# Versterker.net
KiCad netlist of a schematic drawn in Altium Designer
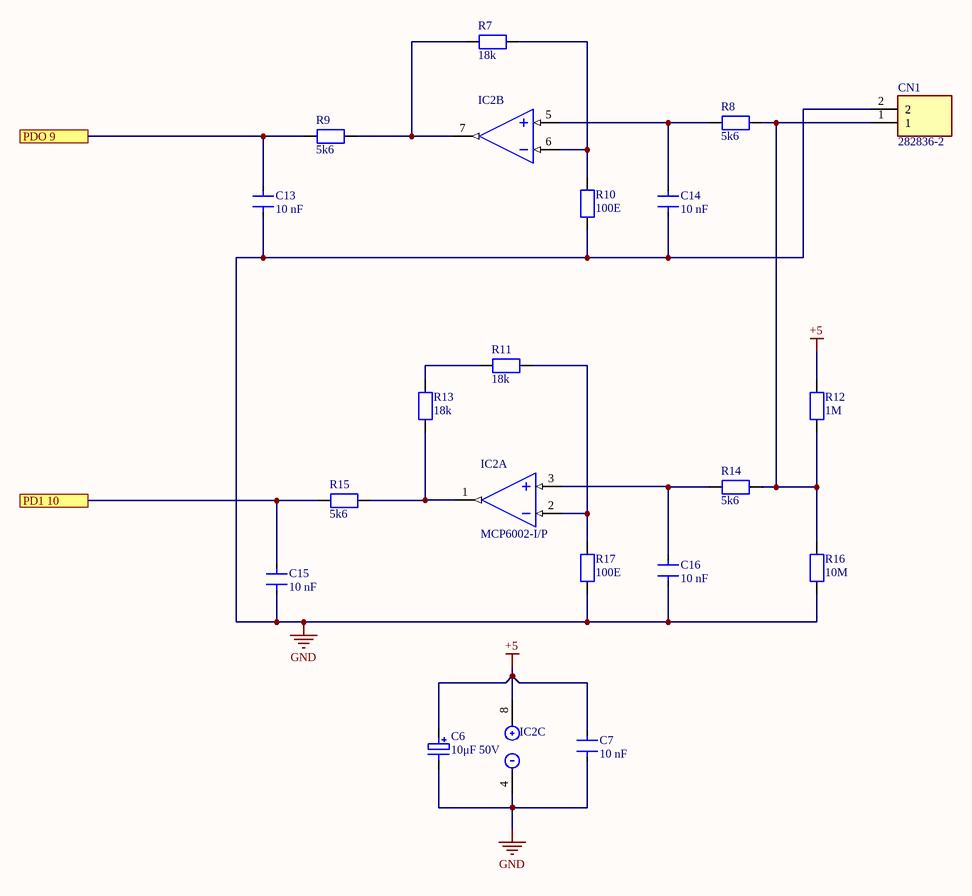
[diagram p0: Versterker.SchDoc]

(export (version "E")
  (design (tool "Eeschema 10.0.6"))
  (components
    (comp (ref "C6")
      (value "10μF 50V")
      (footprint "Elco 10uF 50V")
      (fields
        (field (name "PART NUMBER") "02015A270JAT2A")
        (field (name "MANUFACTURER") "AVX Interconnect / Elco")
      )
      (libsource (lib "Soldeerstation") (part "Condensator Elco"))
    )
    (comp (ref "C7")
      (value "10 nF")
      (footprint "0805")
      (description "Chip Multilayer Ceramic Capacitors for General Purpose, 0805, 10uF, X5R, 15%, 10%, 25V")
      (fields (field (name "VOLTAGE") "25V") (field (name "TOLERANCE") "10%"))
      (libsource (lib "Soldeerstation") (part "Condensator 0805"))
    )
    (comp (ref "C13")
      (value "10 nF")
      (footprint "0805")
      (description "Chip Multilayer Ceramic Capacitors for General Purpose, 0805, 10uF, X5R, 15%, 10%, 25V")
      (fields (field (name "VOLTAGE") "25V") (field (name "TOLERANCE") "10%"))
      (libsource (lib "Soldeerstation") (part "Condensator 0805"))
    )
    (comp (ref "C14")
      (value "10 nF")
      (footprint "0805")
      (description "Chip Multilayer Ceramic Capacitors for General Purpose, 0805, 10uF, X5R, 15%, 10%, 25V")
      (fields (field (name "VOLTAGE") "25V") (field (name "TOLERANCE") "10%"))
      (libsource (lib "Soldeerstation") (part "Condensator 0805"))
    )
    (comp (ref "C15")
      (value "10 nF")
      (footprint "0805")
      (description "Chip Multilayer Ceramic Capacitors for General Purpose, 0805, 10uF, X5R, 15%, 10%, 25V")
      (fields (field (name "VOLTAGE") "25V") (field (name "TOLERANCE") "10%"))
      (libsource (lib "Soldeerstation") (part "Condensator 0805"))
    )
    (comp (ref "C16")
      (value "10 nF")
      (footprint "0805")
      (description "Chip Multilayer Ceramic Capacitors for General Purpose, 0805, 10uF, X5R, 15%, 10%, 25V")
      (fields (field (name "VOLTAGE") "25V") (field (name "TOLERANCE") "10%"))
      (libsource (lib "Soldeerstation") (part "Condensator 0805"))
    )
    (comp (ref "CN1")
      (value "282836-2")
      (footprint "Schroefconnector 2 Pin")
      (description "Connector")
      (libsource (lib "Soldeerstation") (part "Schroefconnector 2 Pin L"))
    )
    (comp (ref "IC2")
      (value "MCP6002-I/P")
      (footprint "Opamp")
      (description "AMP-OPA-MCP6002-IL8")
      (libsource (lib "Soldeerstation") (part "Opamp"))
    )
    (comp (ref "R7")
      (value "18k")
      (footprint "Resistor")
      (description "Resistor")
      (fields (field (name "MANUFACTURER") "Vishay Dale") (field (name "PART NUMBER") "CRCW08050000Z0EA"))
      (libsource (lib "Soldeerstation") (part "Resistor"))
    )
    (comp (ref "R8")
      (value "5k6")
      (footprint "Resistor")
      (description "Resistor")
      (fields (field (name "MANUFACTURER") "Vishay Dale") (field (name "PART NUMBER") "CRCW08050000Z0EA"))
      (libsource (lib "Soldeerstation") (part "Resistor"))
    )
    (comp (ref "R9")
      (value "5k6")
      (footprint "Resistor")
      (description "Resistor")
      (fields (field (name "MANUFACTURER") "Vishay Dale") (field (name "PART NUMBER") "CRCW08050000Z0EA"))
      (libsource (lib "Soldeerstation") (part "Resistor"))
    )
    (comp (ref "R10")
      (value "100E")
      (footprint "Resistor")
      (description "Resistor")
      (fields (field (name "MANUFACTURER") "Vishay Dale") (field (name "PART NUMBER") "CRCW08050000Z0EA"))
      (libsource (lib "Soldeerstation") (part "Resistor"))
    )
    (comp (ref "R11")
      (value "18k")
      (footprint "Resistor")
      (description "Resistor")
      (fields (field (name "MANUFACTURER") "Vishay Dale") (field (name "PART NUMBER") "CRCW08050000Z0EA"))
      (libsource (lib "Soldeerstation") (part "Resistor"))
    )
    (comp (ref "R12")
      (value "1M")
      (footprint "Resistor")
      (description "Resistor")
      (fields (field (name "MANUFACTURER") "Vishay Dale") (field (name "PART NUMBER") "CRCW08050000Z0EA"))
      (libsource (lib "Soldeerstation") (part "Resistor"))
    )
    (comp (ref "R13")
      (value "18k")
      (footprint "Resistor")
      (description "Resistor")
      (fields (field (name "MANUFACTURER") "Vishay Dale") (field (name "PART NUMBER") "CRCW08050000Z0EA"))
      (libsource (lib "Soldeerstation") (part "Resistor"))
    )
    (comp (ref "R14")
      (value "5k6")
      (footprint "Resistor")
      (description "Resistor")
      (fields (field (name "MANUFACTURER") "Vishay Dale") (field (name "PART NUMBER") "CRCW08050000Z0EA"))
      (libsource (lib "Soldeerstation") (part "Resistor"))
    )
    (comp (ref "R15")
      (value "5k6")
      (footprint "Resistor")
      (description "Resistor")
      (fields (field (name "MANUFACTURER") "Vishay Dale") (field (name "PART NUMBER") "CRCW08050000Z0EA"))
      (libsource (lib "Soldeerstation") (part "Resistor"))
    )
    (comp (ref "R16")
      (value "10M")
      (footprint "Resistor")
      (description "Resistor")
      (fields (field (name "MANUFACTURER") "Vishay Dale") (field (name "PART NUMBER") "CRCW08050000Z0EA"))
      (libsource (lib "Soldeerstation") (part "Resistor"))
    )
    (comp (ref "R17")
      (value "100E")
      (footprint "Resistor")
      (description "Resistor")
      (fields (field (name "MANUFACTURER") "Vishay Dale") (field (name "PART NUMBER") "CRCW08050000Z0EA"))
      (libsource (lib "Soldeerstation") (part "Resistor"))
    )
  )
  (nets
    (net (code "1") (name "+5") (class "Default")
      (node (ref "C6") (pin "1") (pinfunction "1_1") (pintype "passive"))
      (node (ref "C7") (pin "2") (pinfunction "2_2") (pintype "passive"))
      (node (ref "IC2") (pin "8") (pintype "power_in"))
      (node (ref "R12") (pin "2") (pinfunction "2_2") (pintype "passive"))
    )
    (net (code "2") (name "/PD1 10") (class "Default")
      (node (ref "C15") (pin "2") (pinfunction "2_2") (pintype "passive"))
      (node (ref "R15") (pin "2") (pinfunction "2_2") (pintype "passive"))
    )
    (net (code "3") (name "/PDO 9") (class "Default")
      (node (ref "C13") (pin "2") (pinfunction "2_2") (pintype "passive"))
      (node (ref "R9") (pin "1") (pintype "passive"))
    )
    (net (code "4") (name "GND") (class "Default")
      (node (ref "C13") (pin "1") (pinfunction "1_1") (pintype "passive"))
      (node (ref "C14") (pin "1") (pinfunction "1_1") (pintype "passive"))
      (node (ref "C15") (pin "1") (pinfunction "1_1") (pintype "passive"))
      (node (ref "C16") (pin "1") (pinfunction "1_1") (pintype "passive"))
      (node (ref "C6") (pin "2") (pinfunction "2_2") (pintype "passive"))
      (node (ref "C7") (pin "1") (pinfunction "1_1") (pintype "passive"))
      (node (ref "CN1") (pin "2") (pinfunction "2_2") (pintype "passive"))
      (node (ref "IC2") (pin "4") (pintype "power_in"))
      (node (ref "R10") (pin "1") (pintype "passive"))
      (node (ref "R16") (pin "1") (pintype "passive"))
      (node (ref "R17") (pin "1") (pintype "passive"))
    )
    (net (code "5") (name "Net-(C14-Pad2)") (class "Default")
      (node (ref "C14") (pin "2") (pinfunction "2_2") (pintype "passive"))
      (node (ref "IC2") (pin "5") (pintype "input"))
      (node (ref "R8") (pin "1") (pintype "passive"))
    )
    (net (code "6") (name "Net-(C16-Pad2)") (class "Default")
      (node (ref "C16") (pin "2") (pinfunction "2_2") (pintype "passive"))
      (node (ref "IC2") (pin "3") (pintype "input"))
      (node (ref "R14") (pin "1") (pintype "passive"))
    )
    (net (code "7") (name "Net-(CN1-Pad1)") (class "Default")
      (node (ref "CN1") (pin "1") (pinfunction "1_1") (pintype "passive"))
      (node (ref "R12") (pin "1") (pintype "passive"))
      (node (ref "R14") (pin "2") (pinfunction "2_2") (pintype "passive"))
      (node (ref "R16") (pin "2") (pinfunction "2_2") (pintype "passive"))
      (node (ref "R8") (pin "2") (pinfunction "2_2") (pintype "passive"))
    )
    (net (code "8") (name "Net-(IC2-Pad1)") (class "Default")
      (node (ref "IC2") (pin "1") (pintype "output"))
      (node (ref "R13") (pin "1") (pintype "passive"))
      (node (ref "R15") (pin "1") (pintype "passive"))
    )
    (net (code "9") (name "Net-(IC2-Pad2)") (class "Default")
      (node (ref "IC2") (pin "2") (pintype "input"))
      (node (ref "R11") (pin "2") (pinfunction "2_2") (pintype "passive"))
      (node (ref "R17") (pin "2") (pinfunction "2_2") (pintype "passive"))
    )
    (net (code "10") (name "Net-(IC2-Pad6)") (class "Default")
      (node (ref "IC2") (pin "6") (pintype "input"))
      (node (ref "R10") (pin "2") (pinfunction "2_2") (pintype "passive"))
      (node (ref "R7") (pin "2") (pinfunction "2_2") (pintype "passive"))
    )
    (net (code "11") (name "Net-(IC2-Pad7)") (class "Default")
      (node (ref "IC2") (pin "7") (pintype "output"))
      (node (ref "R7") (pin "1") (pintype "passive"))
      (node (ref "R9") (pin "2") (pinfunction "2_2") (pintype "passive"))
    )
    (net (code "12") (name "Net-(R11-Pad1)") (class "Default")
      (node (ref "R11") (pin "1") (pintype "passive"))
      (node (ref "R13") (pin "2") (pinfunction "2_2") (pintype "passive"))
    )
  )
)
